# Sheet1.net
KiCad netlist of a schematic drawn in Altium Designer
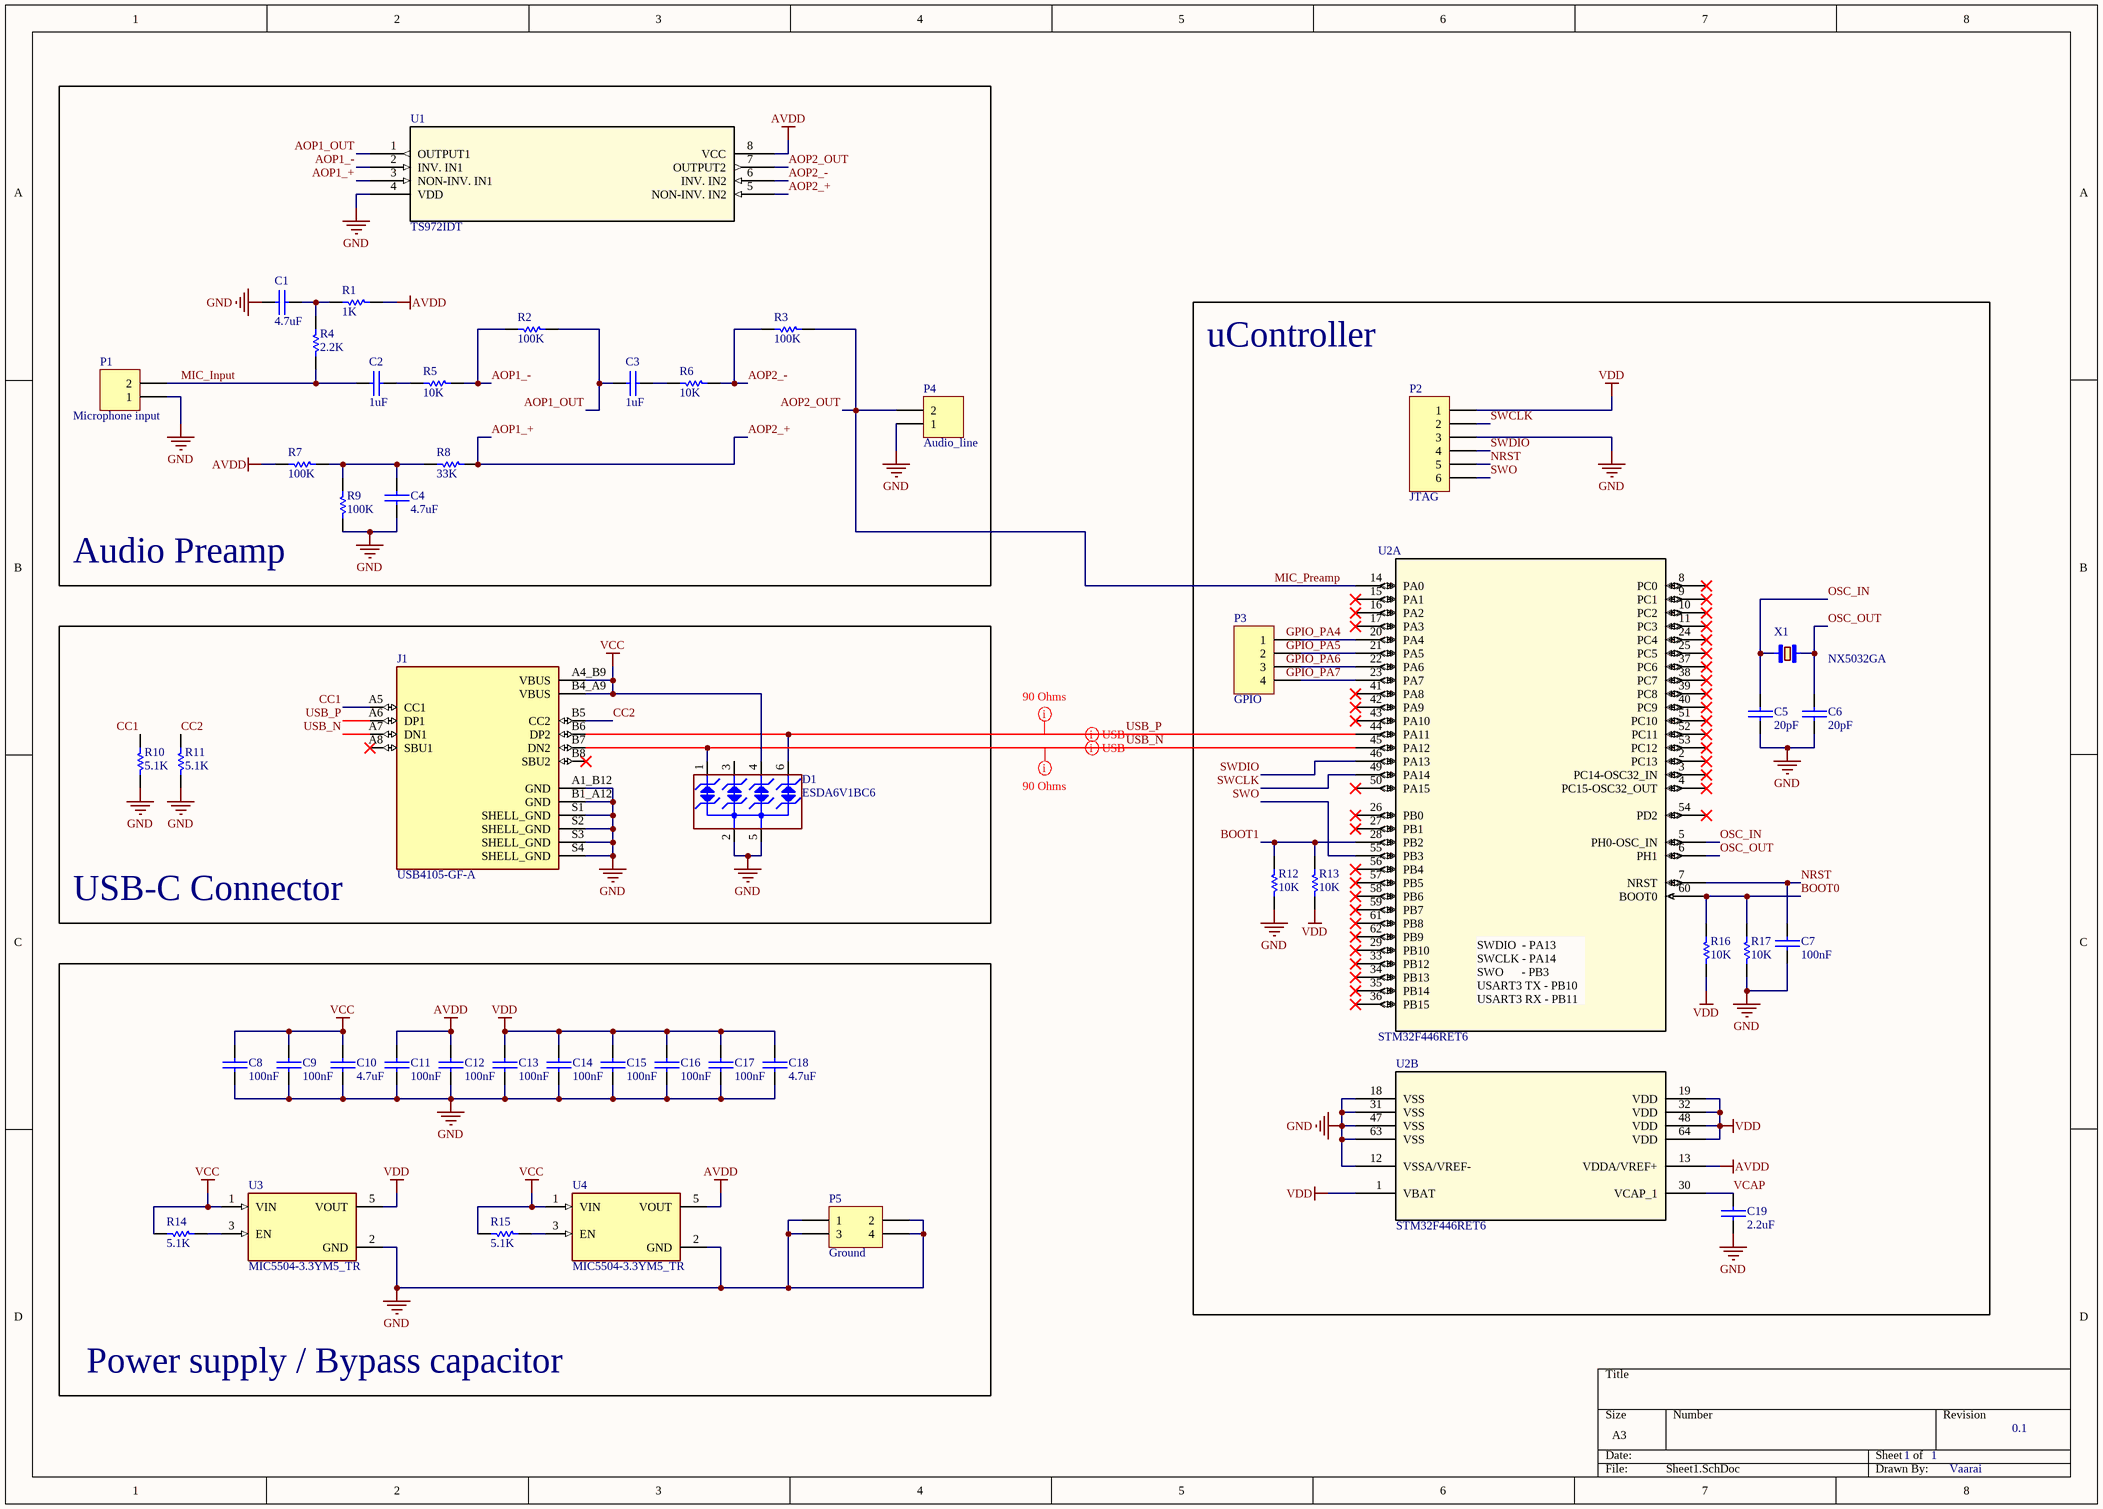
[diagram p0: Sheet1.SchDoc]

(export (version "E")
  (design (tool "Eeschema 10.0.6"))
  (components
    (comp (ref "C1")
      (value "4.7uF")
      (footprint "0603C")
      (description "Capacitor")
      (libsource (lib "MB1137") (part "CAP"))
    )
    (comp (ref "C2")
      (value "1uF")
      (footprint "0603C")
      (description "Capacitor")
      (libsource (lib "MB1137") (part "CAP"))
    )
    (comp (ref "C3")
      (value "1uF")
      (footprint "0603C")
      (description "Capacitor")
      (libsource (lib "MB1137") (part "CAP"))
    )
    (comp (ref "C4")
      (value "4.7uF")
      (footprint "0603C")
      (description "Capacitor")
      (libsource (lib "MB1137") (part "CAP"))
    )
    (comp (ref "C5")
      (value "20pF")
      (footprint "0603C")
      (description "Capacitor")
      (libsource (lib "MB1137") (part "CAP"))
    )
    (comp (ref "C6")
      (value "20pF")
      (footprint "0603C")
      (description "Capacitor")
      (libsource (lib "MB1137") (part "CAP"))
    )
    (comp (ref "C7")
      (value "100nF")
      (footprint "0603C")
      (description "Capacitor")
      (libsource (lib "MB1137") (part "CAP"))
    )
    (comp (ref "C8")
      (value "100nF")
      (footprint "0603C")
      (description "Capacitor")
      (libsource (lib "MB1137") (part "CAP"))
    )
    (comp (ref "C9")
      (value "100nF")
      (footprint "0603C")
      (description "Capacitor")
      (libsource (lib "MB1137") (part "CAP"))
    )
    (comp (ref "C10")
      (value "4.7uF")
      (footprint "0603C")
      (description "Capacitor")
      (libsource (lib "MB1137") (part "CAP"))
    )
    (comp (ref "C11")
      (value "100nF")
      (footprint "0603C")
      (description "Capacitor")
      (libsource (lib "MB1137") (part "CAP"))
    )
    (comp (ref "C12")
      (value "100nF")
      (footprint "0603C")
      (description "Capacitor")
      (libsource (lib "MB1137") (part "CAP"))
    )
    (comp (ref "C13")
      (value "100nF")
      (footprint "0603C")
      (description "Capacitor")
      (libsource (lib "MB1137") (part "CAP"))
    )
    (comp (ref "C14")
      (value "100nF")
      (footprint "0603C")
      (description "Capacitor")
      (libsource (lib "MB1137") (part "CAP"))
    )
    (comp (ref "C15")
      (value "100nF")
      (footprint "0603C")
      (description "Capacitor")
      (libsource (lib "MB1137") (part "CAP"))
    )
    (comp (ref "C16")
      (value "100nF")
      (footprint "0603C")
      (description "Capacitor")
      (libsource (lib "MB1137") (part "CAP"))
    )
    (comp (ref "C17")
      (value "100nF")
      (footprint "0603C")
      (description "Capacitor")
      (libsource (lib "MB1137") (part "CAP"))
    )
    (comp (ref "C18")
      (value "4.7uF")
      (footprint "0603C")
      (description "Capacitor")
      (libsource (lib "MB1137") (part "CAP"))
    )
    (comp (ref "C19")
      (value "2.2uF")
      (footprint "0603C")
      (description "Capacitor")
      (libsource (lib "MB1137") (part "CAP"))
    )
    (comp (ref "D1")
      (value "ESDA6V1BC6")
      (footprint "IC_IC-DP_SOT23-6L:IC_IC-DP_SOT23-6L")
      (description "4-line ESD protection")
      (libsource (lib "MB1137") (part "ESDA6V1BC6"))
    )
    (comp (ref "J1")
      (value "USB4105-GF-A")
      (footprint "GCT_USB4105-GF-A:GCT_USB4105-GF-A")
      (fields (field (name "MF") "GCT"))
      (libsource (lib "USB4105-GF-A") (part "USB4105-GF-A"))
    )
    (comp (ref "P1")
      (value "Microphone input")
      (footprint "HDR1X2")
      (description "Header, 2-Pin")
      (fields (field (name "PUBLISHER") "Altium Limited"))
      (libsource (lib "") (part "Header 2_1"))
    )
    (comp (ref "P2")
      (value "JTAG")
      (footprint "HDR1X6")
      (description "Header, 6-Pin")
      (fields (field (name "PUBLISHER") "Altium Limited"))
      (libsource (lib "Miscellaneous Connectors") (part "Header 6"))
    )
    (comp (ref "P3")
      (value "GPIO")
      (footprint "HDR1X4")
      (description "Header, 4-Pin")
      (fields (field (name "PUBLISHER") "Altium Limited"))
      (libsource (lib "Miscellaneous Connectors") (part "Header 4"))
    )
    (comp (ref "P4")
      (value "Audio_line")
      (footprint "HDR1X2")
      (description "Header, 2-Pin")
      (fields (field (name "PUBLISHER") "Altium Limited"))
      (libsource (lib "Miscellaneous Connectors") (part "Header 2"))
    )
    (comp (ref "P5")
      (value "Ground")
      (footprint "HDR2X2")
      (description "Header, 2-Pin, Dual row")
      (fields (field (name "PUBLISHER") "Altium Limited"))
      (libsource (lib "Miscellaneous Connectors") (part "Header 2X2"))
    )
    (comp (ref "R1")
      (value "1K")
      (footprint "0603R")
      (description "Resistor")
      (fields (field (name "PUBLISHER") "Altium Limited"))
      (libsource (lib "Miscellaneous Devices") (part "Res1"))
    )
    (comp (ref "R2")
      (value "100K")
      (footprint "0603R")
      (description "Resistor")
      (fields (field (name "PUBLISHER") "Altium Limited"))
      (libsource (lib "Miscellaneous Devices") (part "Res1"))
    )
    (comp (ref "R3")
      (value "100K")
      (footprint "0603R")
      (description "Resistor")
      (fields (field (name "PUBLISHER") "Altium Limited"))
      (libsource (lib "Miscellaneous Devices") (part "Res1"))
    )
    (comp (ref "R4")
      (value "2.2K")
      (footprint "0603R")
      (description "Resistor")
      (fields (field (name "PUBLISHER") "Altium Limited"))
      (libsource (lib "Miscellaneous Devices") (part "Res1"))
    )
    (comp (ref "R5")
      (value "10K")
      (footprint "0603R")
      (description "Resistor")
      (fields (field (name "PUBLISHER") "Altium Limited"))
      (libsource (lib "Miscellaneous Devices") (part "Res1"))
    )
    (comp (ref "R6")
      (value "10K")
      (footprint "0603R")
      (description "Resistor")
      (fields (field (name "PUBLISHER") "Altium Limited"))
      (libsource (lib "Miscellaneous Devices") (part "Res1"))
    )
    (comp (ref "R7")
      (value "100K")
      (footprint "0603R")
      (description "Resistor")
      (fields (field (name "PUBLISHER") "Altium Limited"))
      (libsource (lib "Miscellaneous Devices") (part "Res1"))
    )
    (comp (ref "R8")
      (value "33K")
      (footprint "0603R")
      (description "Resistor")
      (fields (field (name "PUBLISHER") "Altium Limited"))
      (libsource (lib "Miscellaneous Devices") (part "Res1"))
    )
    (comp (ref "R9")
      (value "100K")
      (footprint "0603R")
      (description "Resistor")
      (fields (field (name "PUBLISHER") "Altium Limited"))
      (libsource (lib "Miscellaneous Devices") (part "Res1"))
    )
    (comp (ref "R10")
      (value "5.1K")
      (footprint "0603R")
      (description "Resistor")
      (fields (field (name "PUBLISHER") "Altium Limited"))
      (libsource (lib "Miscellaneous Devices") (part "Res1"))
    )
    (comp (ref "R11")
      (value "5.1K")
      (footprint "0603R")
      (description "Resistor")
      (fields (field (name "PUBLISHER") "Altium Limited"))
      (libsource (lib "Miscellaneous Devices") (part "Res1"))
    )
    (comp (ref "R12")
      (value "10K")
      (footprint "0603R")
      (description "Resistor")
      (fields (field (name "PUBLISHER") "Altium Limited"))
      (libsource (lib "Miscellaneous Devices") (part "Res1"))
    )
    (comp (ref "R13")
      (value "10K")
      (footprint "0603R")
      (description "Resistor")
      (fields (field (name "PUBLISHER") "Altium Limited"))
      (libsource (lib "Miscellaneous Devices") (part "Res1"))
    )
    (comp (ref "R14")
      (value "5.1K")
      (footprint "0603R")
      (description "Resistor")
      (fields (field (name "PUBLISHER") "Altium Limited"))
      (libsource (lib "Miscellaneous Devices") (part "Res1"))
    )
    (comp (ref "R15")
      (value "5.1K")
      (footprint "0603R")
      (description "Resistor")
      (fields (field (name "PUBLISHER") "Altium Limited"))
      (libsource (lib "Miscellaneous Devices") (part "Res1"))
    )
    (comp (ref "R16")
      (value "10K")
      (footprint "0603R")
      (description "Resistor")
      (fields (field (name "PUBLISHER") "Altium Limited"))
      (libsource (lib "Miscellaneous Devices") (part "Res1"))
    )
    (comp (ref "R17")
      (value "10K")
      (footprint "0603R")
      (description "Resistor")
      (fields (field (name "PUBLISHER") "Altium Limited"))
      (libsource (lib "Miscellaneous Devices") (part "Res1"))
    )
    (comp (ref "U1")
      (value "TS972IDT")
      (footprint "SO-8_STM")
      (description "No Description Available")
      (fields (field (name "COPYRIGHT") "Copyright (C) 2021 Ultra Librarian. All rights reserved."))
      (libsource (lib "TS972IDT") (part "TS972IDT"))
    )
    (comp (ref "U2")
      (value "STM32F446RET6")
      (footprint "LQFP64-10x10mm")
      (description "No Description Available")
      (fields (field (name "COPYRIGHT") "Copyright (C) 2021 Ultra Librarian. All rights reserved."))
      (libsource (lib "STM32F446RET6") (part "STM32F446RET6"))
    )
    (comp (ref "U3")
      (value "MIC5504-3.3YM5_TR")
      (footprint "SOT95P280X145-5N:SOT95P280X145-5N")
      (description "Linear Voltage Regulator IC 1 Output 300mA SOT-23-5")
      (fields (field (name "MF") "Microchip") (field (name "MP") "MIC5504-3.3YM5 TR"))
      (libsource (lib "MIC5504-3.3YM5_TR") (part "MIC5504-3.3YM5_TR"))
    )
    (comp (ref "U4")
      (value "MIC5504-3.3YM5_TR")
      (footprint "SOT95P280X145-5N:SOT95P280X145-5N")
      (description "Linear Voltage Regulator IC 1 Output 300mA SOT-23-5")
      (fields (field (name "MF") "Microchip") (field (name "MP") "MIC5504-3.3YM5 TR"))
      (libsource (lib "MIC5504-3.3YM5_TR") (part "MIC5504-3.3YM5_TR"))
    )
    (comp (ref "X1")
      (value "NX5032GA")
      (footprint "NX5032GA:2-SMD-5X3")
      (description "16MHz Â±50ppm Crystal 8pF 120 Ohms 2-SMD, No Lead")
      (fields (field (name "MF") "NDK America,"))
      (libsource (lib "NX5032GA") (part "NX5032GA"))
    )
  )
  (nets
    (net (code "1") (name "/AOP1_+") (class "Default")
      (node (ref "R8") (pin "2") (pinfunction "2_2") (pintype "passive"))
      (node (ref "U1") (pin "3") (pinfunction "NON-INV._IN1_3") (pintype "input"))
      (node (ref "U1") (pin "5") (pinfunction "NON-INV._IN2_5") (pintype "input"))
    )
    (net (code "2") (name "/AOP1_-") (class "Default")
      (node (ref "R2") (pin "1") (pinfunction "1_1") (pintype "passive"))
      (node (ref "R5") (pin "2") (pinfunction "2_2") (pintype "passive"))
      (node (ref "U1") (pin "2") (pinfunction "INV._IN1_2") (pintype "input"))
    )
    (net (code "3") (name "/AOP1_OUT") (class "Default")
      (node (ref "C3") (pin "1") (pinfunction "1_1") (pintype "passive"))
      (node (ref "R2") (pin "2") (pinfunction "2_2") (pintype "passive"))
      (node (ref "U1") (pin "1") (pinfunction "OUTPUT1_1") (pintype "output"))
    )
    (net (code "4") (name "/AOP2_-") (class "Default")
      (node (ref "R3") (pin "1") (pinfunction "1_1") (pintype "passive"))
      (node (ref "R6") (pin "2") (pinfunction "2_2") (pintype "passive"))
      (node (ref "U1") (pin "6") (pinfunction "INV._IN2_6") (pintype "input"))
    )
    (net (code "5") (name "/AOP2_OUT") (class "Default")
      (node (ref "P4") (pin "2") (pinfunction "2_2") (pintype "passive"))
      (node (ref "R3") (pin "2") (pinfunction "2_2") (pintype "passive"))
      (node (ref "U1") (pin "7") (pinfunction "OUTPUT2_7") (pintype "output"))
      (node (ref "U2") (pin "14") (pinfunction "PA0_14") (pintype "bidirectional"))
    )
    (net (code "6") (name "/BOOT0") (class "Default")
      (node (ref "R16") (pin "2") (pinfunction "2_2") (pintype "passive"))
      (node (ref "R17") (pin "2") (pinfunction "2_2") (pintype "passive"))
      (node (ref "U2") (pin "60") (pinfunction "BOOT0_60") (pintype "input"))
    )
    (net (code "7") (name "/BOOT1") (class "Default")
      (node (ref "R12") (pin "2") (pinfunction "2_2") (pintype "passive"))
      (node (ref "R13") (pin "2") (pinfunction "2_2") (pintype "passive"))
      (node (ref "U2") (pin "28") (pinfunction "PB2_28") (pintype "bidirectional"))
    )
    (net (code "8") (name "/CC1") (class "Default")
      (node (ref "J1") (pin "A5") (pinfunction "CC1_A5") (pintype "bidirectional"))
      (node (ref "R10") (pin "2") (pinfunction "2_2") (pintype "passive"))
    )
    (net (code "9") (name "/CC2") (class "Default")
      (node (ref "J1") (pin "B5") (pinfunction "CC2_B5") (pintype "bidirectional"))
      (node (ref "R11") (pin "1") (pinfunction "1_1") (pintype "passive"))
    )
    (net (code "10") (name "/GPIO_PA4") (class "Default")
      (node (ref "P3") (pin "1") (pinfunction "1_1") (pintype "passive"))
      (node (ref "U2") (pin "20") (pinfunction "PA4_20") (pintype "bidirectional"))
    )
    (net (code "11") (name "/GPIO_PA5") (class "Default")
      (node (ref "P3") (pin "2") (pinfunction "2_2") (pintype "passive"))
      (node (ref "U2") (pin "21") (pinfunction "PA5_21") (pintype "bidirectional"))
    )
    (net (code "12") (name "/GPIO_PA6") (class "Default")
      (node (ref "P3") (pin "3") (pinfunction "3_3") (pintype "passive"))
      (node (ref "U2") (pin "22") (pinfunction "PA6_22") (pintype "bidirectional"))
    )
    (net (code "13") (name "/GPIO_PA7") (class "Default")
      (node (ref "P3") (pin "4") (pinfunction "4_4") (pintype "passive"))
      (node (ref "U2") (pin "23") (pinfunction "PA7_23") (pintype "bidirectional"))
    )
    (net (code "14") (name "/MIC_Input") (class "Default")
      (node (ref "C2") (pin "1") (pinfunction "1_1") (pintype "passive"))
      (node (ref "P1") (pin "2") (pinfunction "2_2") (pintype "passive"))
      (node (ref "R4") (pin "1") (pinfunction "1_1") (pintype "passive"))
    )
    (net (code "15") (name "/NRST") (class "Default")
      (node (ref "C7") (pin "1") (pinfunction "1_1") (pintype "passive"))
      (node (ref "P2") (pin "5") (pinfunction "5_5") (pintype "passive"))
      (node (ref "U2") (pin "7") (pinfunction "NRST_7") (pintype "bidirectional"))
    )
    (net (code "16") (name "/OSC_IN") (class "Default")
      (node (ref "C5") (pin "1") (pinfunction "1_1") (pintype "passive"))
      (node (ref "U2") (pin "5") (pinfunction "PH0-OSC_IN_5") (pintype "bidirectional"))
      (node (ref "X1") (pin "1") (pinfunction "1_1") (pintype "passive"))
    )
    (net (code "17") (name "/OSC_OUT") (class "Default")
      (node (ref "C6") (pin "1") (pinfunction "1_1") (pintype "passive"))
      (node (ref "U2") (pin "6") (pinfunction "PH1_6") (pintype "bidirectional"))
      (node (ref "X1") (pin "2") (pinfunction "2_2") (pintype "passive"))
    )
    (net (code "18") (name "/SWCLK") (class "Default")
      (node (ref "P2") (pin "2") (pinfunction "2_2") (pintype "passive"))
      (node (ref "U2") (pin "49") (pinfunction "PA14_49") (pintype "bidirectional"))
    )
    (net (code "19") (name "/SWDIO") (class "Default")
      (node (ref "P2") (pin "4") (pinfunction "4_4") (pintype "passive"))
      (node (ref "U2") (pin "46") (pinfunction "PA13_46") (pintype "bidirectional"))
    )
    (net (code "20") (name "/SWO") (class "Default")
      (node (ref "P2") (pin "6") (pinfunction "6_6") (pintype "passive"))
      (node (ref "U2") (pin "55") (pinfunction "PB3_55") (pintype "bidirectional"))
    )
    (net (code "21") (name "/USB_N") (class "Default")
      (node (ref "D1") (pin "1") (pinfunction "IO1_1") (pintype "passive"))
      (node (ref "J1") (pin "A7") (pinfunction "DN1_A7") (pintype "bidirectional"))
      (node (ref "J1") (pin "B7") (pinfunction "DN2_B7") (pintype "bidirectional"))
      (node (ref "U2") (pin "45") (pinfunction "PA12_45") (pintype "bidirectional"))
    )
    (net (code "22") (name "/USB_P") (class "Default")
      (node (ref "D1") (pin "6") (pinfunction "NC_6") (pintype "passive"))
      (node (ref "J1") (pin "A6") (pinfunction "DP1_A6") (pintype "bidirectional"))
      (node (ref "J1") (pin "B6") (pinfunction "DP2_B6") (pintype "bidirectional"))
      (node (ref "U2") (pin "44") (pinfunction "PA11_44") (pintype "bidirectional"))
    )
    (net (code "23") (name "/VCAP") (class "Default")
      (node (ref "C19") (pin "1") (pinfunction "1_1") (pintype "passive"))
      (node (ref "U2") (pin "30") (pinfunction "VCAP_1_30") (pintype "power_in"))
    )
    (net (code "24") (name "AVDD") (class "Default")
      (node (ref "C11") (pin "1") (pinfunction "1_1") (pintype "passive"))
      (node (ref "C12") (pin "1") (pinfunction "1_1") (pintype "passive"))
      (node (ref "R1") (pin "2") (pinfunction "2_2") (pintype "passive"))
      (node (ref "R7") (pin "2") (pinfunction "2_2") (pintype "passive"))
      (node (ref "U1") (pin "8") (pinfunction "VCC_8") (pintype "power_in"))
      (node (ref "U2") (pin "13") (pinfunction "VDDA/VREF+_13") (pintype "power_in"))
      (node (ref "U4") (pin "5") (pinfunction "VOUT_5") (pintype "power_in"))
    )
    (net (code "25") (name "GND") (class "Default")
      (node (ref "C1") (pin "2") (pinfunction "2_2") (pintype "passive"))
      (node (ref "C10") (pin "2") (pinfunction "2_2") (pintype "passive"))
      (node (ref "C11") (pin "2") (pinfunction "2_2") (pintype "passive"))
      (node (ref "C12") (pin "2") (pinfunction "2_2") (pintype "passive"))
      (node (ref "C13") (pin "2") (pinfunction "2_2") (pintype "passive"))
      (node (ref "C14") (pin "2") (pinfunction "2_2") (pintype "passive"))
      (node (ref "C15") (pin "2") (pinfunction "2_2") (pintype "passive"))
      (node (ref "C16") (pin "2") (pinfunction "2_2") (pintype "passive"))
      (node (ref "C17") (pin "2") (pinfunction "2_2") (pintype "passive"))
      (node (ref "C18") (pin "2") (pinfunction "2_2") (pintype "passive"))
      (node (ref "C19") (pin "2") (pinfunction "2_2") (pintype "passive"))
      (node (ref "C4") (pin "2") (pinfunction "2_2") (pintype "passive"))
      (node (ref "C5") (pin "2") (pinfunction "2_2") (pintype "passive"))
      (node (ref "C6") (pin "2") (pinfunction "2_2") (pintype "passive"))
      (node (ref "C7") (pin "2") (pinfunction "2_2") (pintype "passive"))
      (node (ref "C8") (pin "2") (pinfunction "2_2") (pintype "passive"))
      (node (ref "C9") (pin "2") (pinfunction "2_2") (pintype "passive"))
      (node (ref "D1") (pin "2") (pinfunction "IO2_2") (pintype "passive"))
      (node (ref "D1") (pin "5") (pinfunction "IO4_5") (pintype "passive"))
      (node (ref "J1") (pin "A1_B12") (pinfunction "GND_A1_B12") (pintype "power_in"))
      (node (ref "J1") (pin "B1_A12") (pinfunction "GND_B1_A12") (pintype "power_in"))
      (node (ref "J1") (pin "S1") (pinfunction "SHELL_GND_S1") (pintype "power_in"))
      (node (ref "J1") (pin "S2") (pinfunction "SHELL_GND_S2") (pintype "power_in"))
      (node (ref "J1") (pin "S3") (pinfunction "SHELL_GND_S3") (pintype "power_in"))
      (node (ref "J1") (pin "S4") (pinfunction "SHELL_GND_S4") (pintype "power_in"))
      (node (ref "P1") (pin "1") (pinfunction "1_1") (pintype "passive"))
      (node (ref "P2") (pin "3") (pinfunction "3_3") (pintype "passive"))
      (node (ref "P4") (pin "1") (pinfunction "1_1") (pintype "passive"))
      (node (ref "P5") (pin "1") (pinfunction "1_1") (pintype "passive"))
      (node (ref "P5") (pin "2") (pinfunction "2_2") (pintype "passive"))
      (node (ref "P5") (pin "3") (pinfunction "3_3") (pintype "passive"))
      (node (ref "P5") (pin "4") (pinfunction "4_4") (pintype "passive"))
      (node (ref "R10") (pin "1") (pinfunction "1_1") (pintype "passive"))
      (node (ref "R11") (pin "2") (pinfunction "2_2") (pintype "passive"))
      (node (ref "R12") (pin "1") (pinfunction "1_1") (pintype "passive"))
      (node (ref "R17") (pin "1") (pinfunction "1_1") (pintype "passive"))
      (node (ref "R9") (pin "1") (pinfunction "1_1") (pintype "passive"))
      (node (ref "U1") (pin "4") (pinfunction "VDD_4") (pintype "power_in"))
      (node (ref "U2") (pin "12") (pinfunction "VSSA/VREF-_12") (pintype "power_in"))
      (node (ref "U2") (pin "18") (pinfunction "VSS_18") (pintype "power_in"))
      (node (ref "U2") (pin "31") (pinfunction "VSS_31") (pintype "power_in"))
      (node (ref "U2") (pin "47") (pinfunction "VSS_47") (pintype "power_in"))
      (node (ref "U2") (pin "63") (pinfunction "VSS_63") (pintype "power_in"))
      (node (ref "U3") (pin "2") (pinfunction "GND_2") (pintype "power_in"))
      (node (ref "U4") (pin "2") (pinfunction "GND_2") (pintype "power_in"))
    )
    (net (code "26") (name "Net-(C1-Pad1)") (class "Default")
      (node (ref "C1") (pin "1") (pinfunction "1_1") (pintype "passive"))
      (node (ref "R1") (pin "1") (pinfunction "1_1") (pintype "passive"))
      (node (ref "R4") (pin "2") (pinfunction "2_2") (pintype "passive"))
    )
    (net (code "27") (name "Net-(C2-Pad2)") (class "Default")
      (node (ref "C2") (pin "2") (pinfunction "2_2") (pintype "passive"))
      (node (ref "R5") (pin "1") (pinfunction "1_1") (pintype "passive"))
    )
    (net (code "28") (name "Net-(C3-Pad2)") (class "Default")
      (node (ref "C3") (pin "2") (pinfunction "2_2") (pintype "passive"))
      (node (ref "R6") (pin "1") (pinfunction "1_1") (pintype "passive"))
    )
    (net (code "29") (name "Net-(C4-Pad1)") (class "Default")
      (node (ref "C4") (pin "1") (pinfunction "1_1") (pintype "passive"))
      (node (ref "R7") (pin "1") (pinfunction "1_1") (pintype "passive"))
      (node (ref "R8") (pin "1") (pinfunction "1_1") (pintype "passive"))
      (node (ref "R9") (pin "2") (pinfunction "2_2") (pintype "passive"))
    )
    (net (code "30") (name "Net-(U3-EN)") (class "Default")
      (node (ref "R14") (pin "2") (pinfunction "2_2") (pintype "passive"))
      (node (ref "U3") (pin "3") (pinfunction "EN_3") (pintype "input"))
    )
    (net (code "31") (name "Net-(U4-EN)") (class "Default")
      (node (ref "R15") (pin "2") (pinfunction "2_2") (pintype "passive"))
      (node (ref "U4") (pin "3") (pinfunction "EN_3") (pintype "input"))
    )
    (net (code "32") (name "VCC") (class "Default")
      (node (ref "C10") (pin "1") (pinfunction "1_1") (pintype "passive"))
      (node (ref "C8") (pin "1") (pinfunction "1_1") (pintype "passive"))
      (node (ref "C9") (pin "1") (pinfunction "1_1") (pintype "passive"))
      (node (ref "D1") (pin "4") (pinfunction "IO3_4") (pintype "passive"))
      (node (ref "J1") (pin "A4_B9") (pinfunction "VBUS_A4_B9") (pintype "power_in"))
      (node (ref "J1") (pin "B4_A9") (pinfunction "VBUS_B4_A9") (pintype "power_in"))
      (node (ref "R14") (pin "1") (pinfunction "1_1") (pintype "passive"))
      (node (ref "R15") (pin "1") (pinfunction "1_1") (pintype "passive"))
      (node (ref "U3") (pin "1") (pinfunction "VIN_1") (pintype "input"))
      (node (ref "U4") (pin "1") (pinfunction "VIN_1") (pintype "input"))
    )
    (net (code "33") (name "VDD") (class "Default")
      (node (ref "C13") (pin "1") (pinfunction "1_1") (pintype "passive"))
      (node (ref "C14") (pin "1") (pinfunction "1_1") (pintype "passive"))
      (node (ref "C15") (pin "1") (pinfunction "1_1") (pintype "passive"))
      (node (ref "C16") (pin "1") (pinfunction "1_1") (pintype "passive"))
      (node (ref "C17") (pin "1") (pinfunction "1_1") (pintype "passive"))
      (node (ref "C18") (pin "1") (pinfunction "1_1") (pintype "passive"))
      (node (ref "P2") (pin "1") (pinfunction "1_1") (pintype "passive"))
      (node (ref "R13") (pin "1") (pinfunction "1_1") (pintype "passive"))
      (node (ref "R16") (pin "1") (pinfunction "1_1") (pintype "passive"))
      (node (ref "U2") (pin "1") (pinfunction "VBAT_1") (pintype "power_in"))
      (node (ref "U2") (pin "19") (pinfunction "VDD_19") (pintype "power_in"))
      (node (ref "U2") (pin "32") (pinfunction "VDD_32") (pintype "power_in"))
      (node (ref "U2") (pin "48") (pinfunction "VDD_48") (pintype "power_in"))
      (node (ref "U2") (pin "64") (pinfunction "VDD_64") (pintype "power_in"))
      (node (ref "U3") (pin "5") (pinfunction "VOUT_5") (pintype "power_in"))
    )
    (net (code "34") (name "unconnected-(D1-GND-Pad3)") (class "Default")
      (node (ref "D1") (pin "3") (pinfunction "GND_3") (pintype "passive"))
    )
    (net (code "35") (name "unconnected-(J1-SBU1-PadA8)") (class "Default")
      (node (ref "J1") (pin "A8") (pinfunction "SBU1_A8") (pintype "bidirectional+no_connect"))
    )
    (net (code "36") (name "unconnected-(J1-SBU2-PadB8)") (class "Default")
      (node (ref "J1") (pin "B8") (pinfunction "SBU2_B8") (pintype "bidirectional+no_connect"))
    )
    (net (code "37") (name "unconnected-(U2A-PA1-Pad15)") (class "Default")
      (node (ref "U2") (pin "15") (pinfunction "PA1_15") (pintype "bidirectional+no_connect"))
    )
    (net (code "38") (name "unconnected-(U2A-PA2-Pad16)") (class "Default")
      (node (ref "U2") (pin "16") (pinfunction "PA2_16") (pintype "bidirectional+no_connect"))
    )
    (net (code "39") (name "unconnected-(U2A-PA3-Pad17)") (class "Default")
      (node (ref "U2") (pin "17") (pinfunction "PA3_17") (pintype "bidirectional+no_connect"))
    )
    (net (code "40") (name "unconnected-(U2A-PA8-Pad41)") (class "Default")
      (node (ref "U2") (pin "41") (pinfunction "PA8_41") (pintype "bidirectional+no_connect"))
    )
    (net (code "41") (name "unconnected-(U2A-PA9-Pad42)") (class "Default")
      (node (ref "U2") (pin "42") (pinfunction "PA9_42") (pintype "bidirectional+no_connect"))
    )
    (net (code "42") (name "unconnected-(U2A-PA10-Pad43)") (class "Default")
      (node (ref "U2") (pin "43") (pinfunction "PA10_43") (pintype "bidirectional+no_connect"))
    )
    (net (code "43") (name "unconnected-(U2A-PA15-Pad50)") (class "Default")
      (node (ref "U2") (pin "50") (pinfunction "PA15_50") (pintype "bidirectional+no_connect"))
    )
    (net (code "44") (name "unconnected-(U2A-PB0-Pad26)") (class "Default")
      (node (ref "U2") (pin "26") (pinfunction "PB0_26") (pintype "bidirectional+no_connect"))
    )
    (net (code "45") (name "unconnected-(U2A-PB1-Pad27)") (class "Default")
      (node (ref "U2") (pin "27") (pinfunction "PB1_27") (pintype "bidirectional+no_connect"))
    )
    (net (code "46") (name "unconnected-(U2A-PB4-Pad56)") (class "Default")
      (node (ref "U2") (pin "56") (pinfunction "PB4_56") (pintype "bidirectional+no_connect"))
    )
    (net (code "47") (name "unconnected-(U2A-PB5-Pad57)") (class "Default")
      (node (ref "U2") (pin "57") (pinfunction "PB5_57") (pintype "bidirectional+no_connect"))
    )
    (net (code "48") (name "unconnected-(U2A-PB6-Pad58)") (class "Default")
      (node (ref "U2") (pin "58") (pinfunction "PB6_58") (pintype "bidirectional+no_connect"))
    )
    (net (code "49") (name "unconnected-(U2A-PB7-Pad59)") (class "Default")
      (node (ref "U2") (pin "59") (pinfunction "PB7_59") (pintype "bidirectional+no_connect"))
    )
    (net (code "50") (name "unconnected-(U2A-PB8-Pad61)") (class "Default")
      (node (ref "U2") (pin "61") (pinfunction "PB8_61") (pintype "bidirectional+no_connect"))
    )
    (net (code "51") (name "unconnected-(U2A-PB9-Pad62)") (class "Default")
      (node (ref "U2") (pin "62") (pinfunction "PB9_62") (pintype "bidirectional+no_connect"))
    )
    (net (code "52") (name "unconnected-(U2A-PB10-Pad29)") (class "Default")
      (node (ref "U2") (pin "29") (pinfunction "PB10_29") (pintype "bidirectional+no_connect"))
    )
    (net (code "53") (name "unconnected-(U2A-PB12-Pad33)") (class "Default")
      (node (ref "U2") (pin "33") (pinfunction "PB12_33") (pintype "bidirectional+no_connect"))
    )
    (net (code "54") (name "unconnected-(U2A-PB13-Pad34)") (class "Default")
      (node (ref "U2") (pin "34") (pinfunction "PB13_34") (pintype "bidirectional+no_connect"))
    )
    (net (code "55") (name "unconnected-(U2A-PB14-Pad35)") (class "Default")
      (node (ref "U2") (pin "35") (pinfunction "PB14_35") (pintype "bidirectional+no_connect"))
    )
    (net (code "56") (name "unconnected-(U2A-PB15-Pad36)") (class "Default")
      (node (ref "U2") (pin "36") (pinfunction "PB15_36") (pintype "bidirectional+no_connect"))
    )
    (net (code "57") (name "unconnected-(U2A-PC0-Pad8)") (class "Default")
      (node (ref "U2") (pin "8") (pinfunction "PC0_8") (pintype "bidirectional+no_connect"))
    )
    (net (code "58") (name "unconnected-(U2A-PC1-Pad9)") (class "Default")
      (node (ref "U2") (pin "9") (pinfunction "PC1_9") (pintype "bidirectional+no_connect"))
    )
    (net (code "59") (name "unconnected-(U2A-PC2-Pad10)") (class "Default")
      (node (ref "U2") (pin "10") (pinfunction "PC2_10") (pintype "bidirectional+no_connect"))
    )
    (net (code "60") (name "unconnected-(U2A-PC3-Pad11)") (class "Default")
      (node (ref "U2") (pin "11") (pinfunction "PC3_11") (pintype "bidirectional+no_connect"))
    )
    (net (code "61") (name "unconnected-(U2A-PC4-Pad24)") (class "Default")
      (node (ref "U2") (pin "24") (pinfunction "PC4_24") (pintype "bidirectional+no_connect"))
    )
    (net (code "62") (name "unconnected-(U2A-PC5-Pad25)") (class "Default")
      (node (ref "U2") (pin "25") (pinfunction "PC5_25") (pintype "bidirectional+no_connect"))
    )
    (net (code "63") (name "unconnected-(U2A-PC6-Pad37)") (class "Default")
      (node (ref "U2") (pin "37") (pinfunction "PC6_37") (pintype "bidirectional+no_connect"))
    )
    (net (code "64") (name "unconnected-(U2A-PC7-Pad38)") (class "Default")
      (node (ref "U2") (pin "38") (pinfunction "PC7_38") (pintype "bidirectional+no_connect"))
    )
    (net (code "65") (name "unconnected-(U2A-PC8-Pad39)") (class "Default")
      (node (ref "U2") (pin "39") (pinfunction "PC8_39") (pintype "bidirectional+no_connect"))
    )
    (net (code "66") (name "unconnected-(U2A-PC9-Pad40)") (class "Default")
      (node (ref "U2") (pin "40") (pinfunction "PC9_40") (pintype "bidirectional+no_connect"))
    )
    (net (code "67") (name "unconnected-(U2A-PC10-Pad51)") (class "Default")
      (node (ref "U2") (pin "51") (pinfunction "PC10_51") (pintype "bidirectional+no_connect"))
    )
    (net (code "68") (name "unconnected-(U2A-PC11-Pad52)") (class "Default")
      (node (ref "U2") (pin "52") (pinfunction "PC11_52") (pintype "bidirectional+no_connect"))
    )
    (net (code "69") (name "unconnected-(U2A-PC12-Pad53)") (class "Default")
      (node (ref "U2") (pin "53") (pinfunction "PC12_53") (pintype "bidirectional+no_connect"))
    )
    (net (code "70") (name "unconnected-(U2A-PC13-Pad2)") (class "Default")
      (node (ref "U2") (pin "2") (pinfunction "PC13_2") (pintype "bidirectional+no_connect"))
    )
    (net (code "71") (name "unconnected-(U2A-PC14-OSC32_IN-Pad3)") (class "Default")
      (node (ref "U2") (pin "3") (pinfunction "PC14-OSC32_IN_3") (pintype "bidirectional+no_connect"))
    )
    (net (code "72") (name "unconnected-(U2A-PC15-OSC32_OUT-Pad4)") (class "Default")
      (node (ref "U2") (pin "4") (pinfunction "PC15-OSC32_OUT_4") (pintype "bidirectional+no_connect"))
    )
    (net (code "73") (name "unconnected-(U2A-PD2-Pad54)") (class "Default")
      (node (ref "U2") (pin "54") (pinfunction "PD2_54") (pintype "bidirectional+no_connect"))
    )
  )
)
